# BUFFER_BTOA.net
KiCad netlist of a schematic drawn in Altium Designer
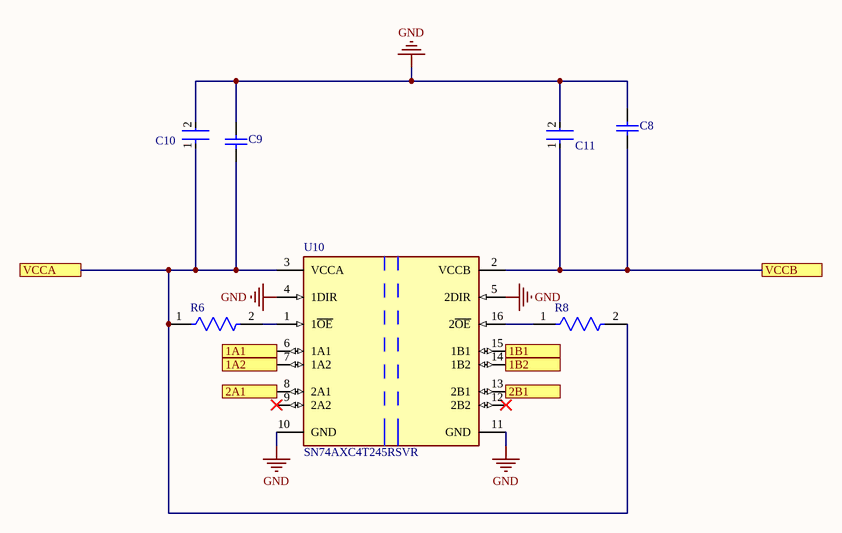
[diagram p0: BUFFER_BTOA.SchDoc]

(export (version "E")
  (design (tool "Eeschema 10.0.6"))
  (components
    (comp (ref "C8")
      (value "CAP 1uF 16V 0805(2012)")
      (footprint "CAPC0805(2012)100_N")
      (description "CAP 1uF 16V ±10% 0805 (2012 Metric) Thickness 1mm SMD")
      (fields (field (name "TOLERANCE") "Â±10%") (field (name "MANUFACTURER") "KEMET"))
      (libsource (lib "Altium Content Vault") (part "CAP"))
    )
    (comp (ref "C9")
      (value "CAP 1uF 16V 0805(2012)")
      (footprint "CAPC0805(2012)100_N")
      (description "CAP 1uF 16V ±10% 0805 (2012 Metric) Thickness 1mm SMD")
      (fields (field (name "TOLERANCE") "Â±10%") (field (name "MANUFACTURER") "KEMET"))
      (libsource (lib "Altium Content Vault") (part "CAP"))
    )
    (comp (ref "C10")
      (value "C0805C104K4RAC")
      (footprint "FP-C0805C-DN-MFG")
      (description "C0805 0.10 μF X7R 30ppm/°C 10.00% 16 V")
      (fields
        (field (name "TOLERANCE") "0.1")
        (field (name "OCTOPART") "https://octopart.com/c0805c104k4rac-kemet-1343167")
      )
      (libsource (lib "Altium Content Vault") (part "b4654b650e69147ec39a6b967a45e02"))
    )
    (comp (ref "C11")
      (value "C0805C104K4RAC")
      (footprint "FP-C0805C-DN-MFG")
      (description "C0805 0.10 μF X7R 30ppm/°C 10.00% 16 V")
      (fields
        (field (name "TOLERANCE") "0.1")
        (field (name "OCTOPART") "https://octopart.com/c0805c104k4rac-kemet-1343167")
      )
      (libsource (lib "Altium Content Vault") (part "b4654b650e69147ec39a6b967a45e02"))
    )
    (comp (ref "R6")
      (value "RC0603FR-0710KL")
      (footprint "FP-RC0603-0_55-IPC_C")
      (description "RES 10K OHM 1% 1/10W 0603")
      (fields (field (name "TOLERANCE") "1%") (field (name "MANUFACTURER") "Yageo"))
      (libsource (lib "Altium Content Vault") (part "1029c3af85768c4190bb7ad29bc67b5"))
    )
    (comp (ref "R8")
      (value "RC0603FR-0710KL")
      (footprint "FP-RC0603-0_55-IPC_C")
      (description "RES 10K OHM 1% 1/10W 0603")
      (fields (field (name "TOLERANCE") "1%") (field (name "MANUFACTURER") "Yageo"))
      (libsource (lib "Altium Content Vault") (part "1029c3af85768c4190bb7ad29bc67b5"))
    )
    (comp (ref "U10")
      (value "SN74AXC4T245RSVR")
      (footprint "FP-RSV0016A-MFG")
      (description "IC TRANSLATION TXRX 3.6V 16UQFN")
      (fields (field (name "MANUFACTURER") "Texas Instruments"))
      (libsource (lib "Altium Content Vault") (part "9aa2af95b06c3ac18b79f12dda9fb43"))
    )
  )
  (nets
    (net (code "1") (name "/1A1") (class "Default")
      (node (ref "U10") (pin "6") (pinfunction "1A1_6") (pintype "bidirectional"))
    )
    (net (code "2") (name "/1A2") (class "Default")
      (node (ref "U10") (pin "7") (pinfunction "1A2_7") (pintype "bidirectional"))
    )
    (net (code "3") (name "/1B1") (class "Default")
      (node (ref "U10") (pin "15") (pinfunction "1B1_15") (pintype "bidirectional"))
    )
    (net (code "4") (name "/1B2") (class "Default")
      (node (ref "U10") (pin "14") (pinfunction "1B2_14") (pintype "bidirectional"))
    )
    (net (code "5") (name "/2A1") (class "Default")
      (node (ref "U10") (pin "8") (pinfunction "2A1_8") (pintype "bidirectional"))
    )
    (net (code "6") (name "/2B1") (class "Default")
      (node (ref "U10") (pin "13") (pinfunction "2B1_13") (pintype "bidirectional"))
    )
    (net (code "7") (name "/VCCA") (class "Default")
      (node (ref "C10") (pin "1") (pinfunction "1_1") (pintype "passive"))
      (node (ref "C9") (pin "1") (pinfunction "1_1") (pintype "passive"))
      (node (ref "R6") (pin "1") (pinfunction "1_1") (pintype "passive"))
      (node (ref "R8") (pin "2") (pinfunction "2_2") (pintype "passive"))
      (node (ref "U10") (pin "3") (pinfunction "VCCA_3") (pintype "power_in"))
    )
    (net (code "8") (name "/VCCB") (class "Default")
      (node (ref "C11") (pin "1") (pinfunction "1_1") (pintype "passive"))
      (node (ref "C8") (pin "1") (pinfunction "1_1") (pintype "passive"))
      (node (ref "U10") (pin "2") (pinfunction "VCCB_2") (pintype "power_in"))
    )
    (net (code "9") (name "GND") (class "Default")
      (node (ref "C10") (pin "2") (pinfunction "2_2") (pintype "passive"))
      (node (ref "C11") (pin "2") (pinfunction "2_2") (pintype "passive"))
      (node (ref "C8") (pin "2") (pinfunction "2_2") (pintype "passive"))
      (node (ref "C9") (pin "2") (pinfunction "2_2") (pintype "passive"))
      (node (ref "U10") (pin "10") (pinfunction "GND_10") (pintype "power_in"))
      (node (ref "U10") (pin "11") (pinfunction "GND_11") (pintype "power_in"))
      (node (ref "U10") (pin "4") (pinfunction "1DIR_4") (pintype "input"))
      (node (ref "U10") (pin "5") (pinfunction "2DIR_5") (pintype "input"))
    )
    (net (code "10") (name "Net-(U10-1~{OE})") (class "Default")
      (node (ref "R6") (pin "2") (pinfunction "2_2") (pintype "passive"))
      (node (ref "U10") (pin "1") (pinfunction "1~{OE}_1") (pintype "input"))
    )
    (net (code "11") (name "Net-(U10-2~{OE})") (class "Default")
      (node (ref "R8") (pin "1") (pinfunction "1_1") (pintype "passive"))
      (node (ref "U10") (pin "16") (pinfunction "2~{OE}_16") (pintype "input"))
    )
    (net (code "12") (name "unconnected-(U10-2A2-Pad9)") (class "Default")
      (node (ref "U10") (pin "9") (pinfunction "2A2_9") (pintype "bidirectional+no_connect"))
    )
    (net (code "13") (name "unconnected-(U10-2B2-Pad12)") (class "Default")
      (node (ref "U10") (pin "12") (pinfunction "2B2_12") (pintype "bidirectional+no_connect"))
    )
  )
)
